# Robot_Arm_Controller.net
KiCad netlist of a schematic drawn in EAGLE
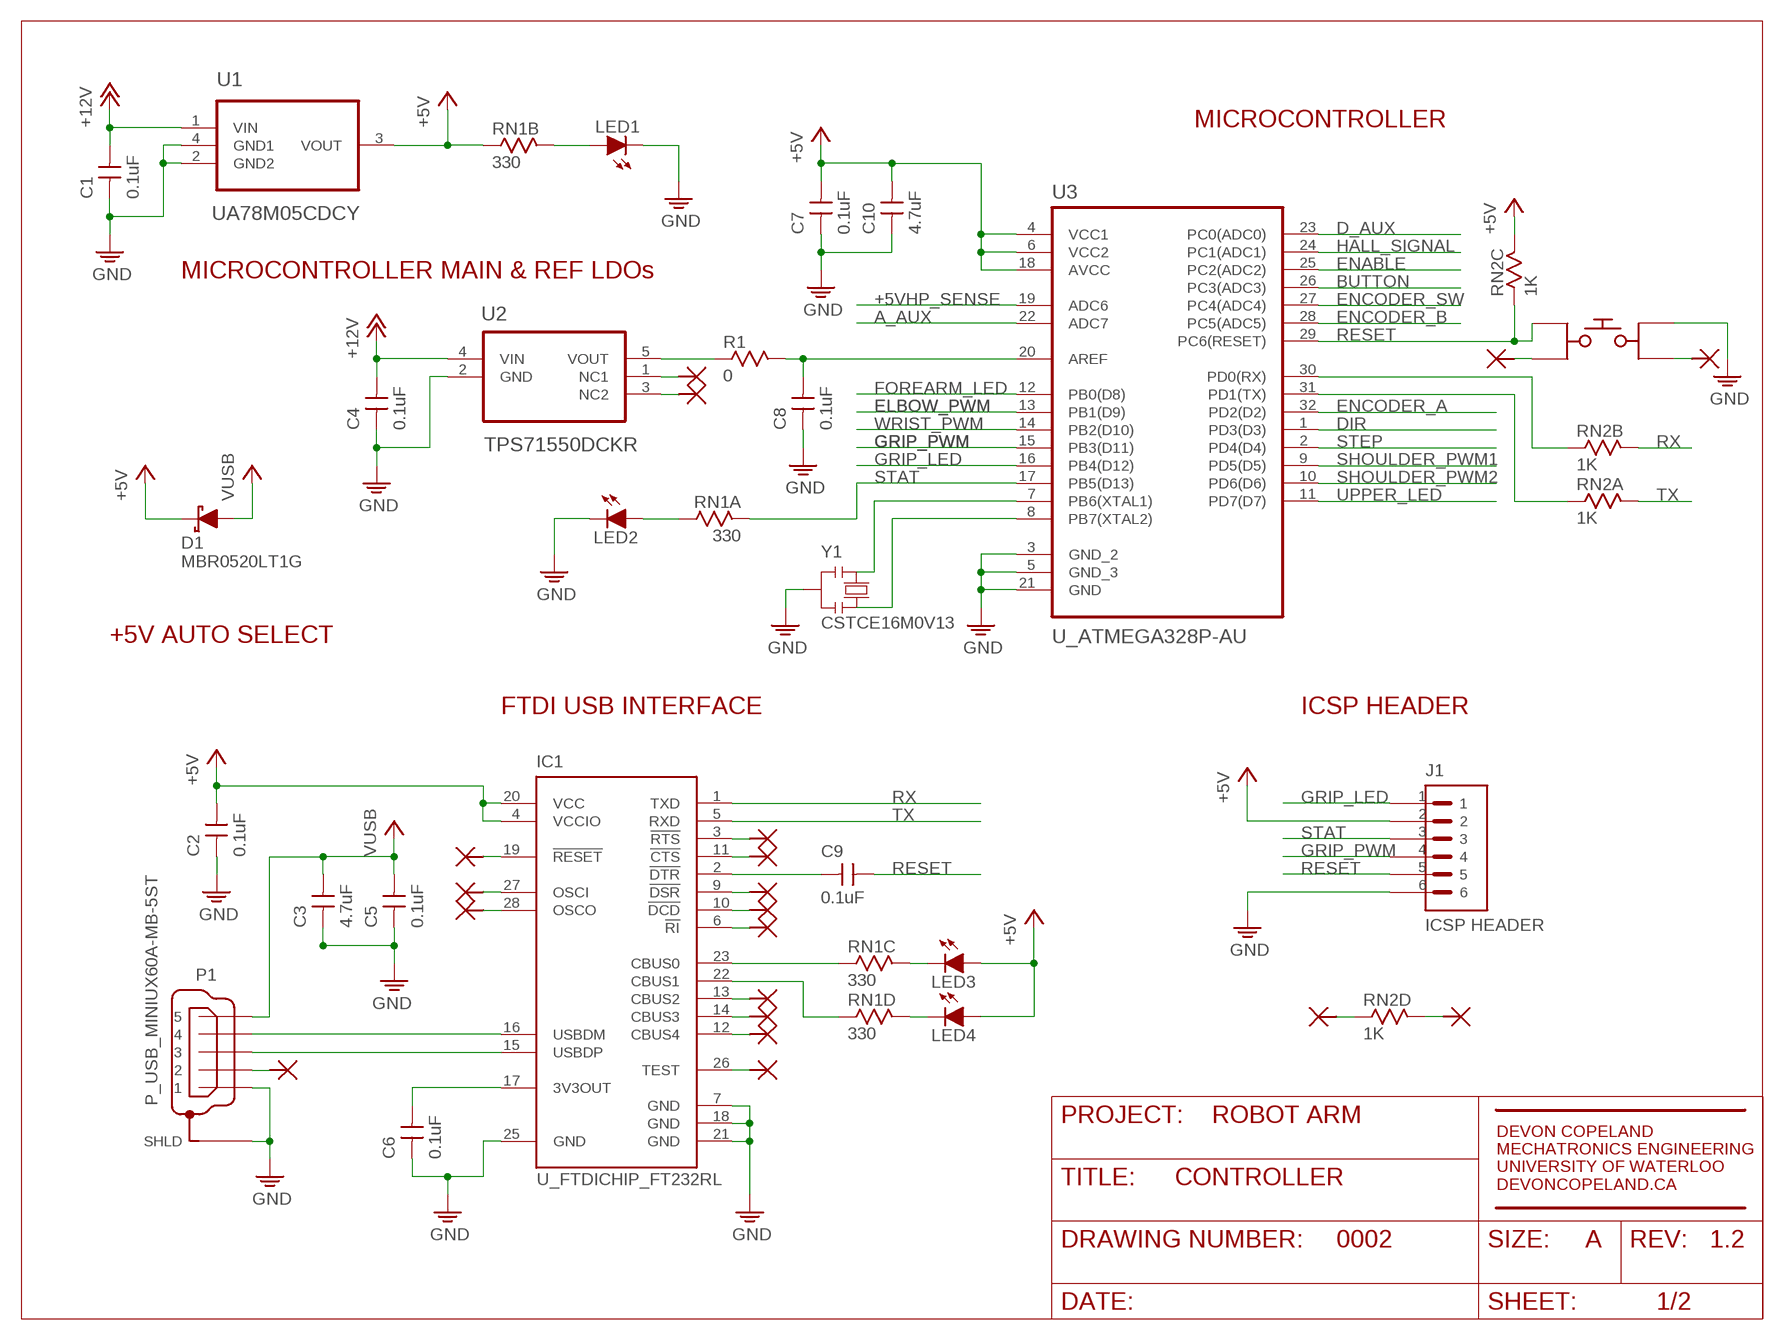
[diagram p0: schematic, sheet 1]
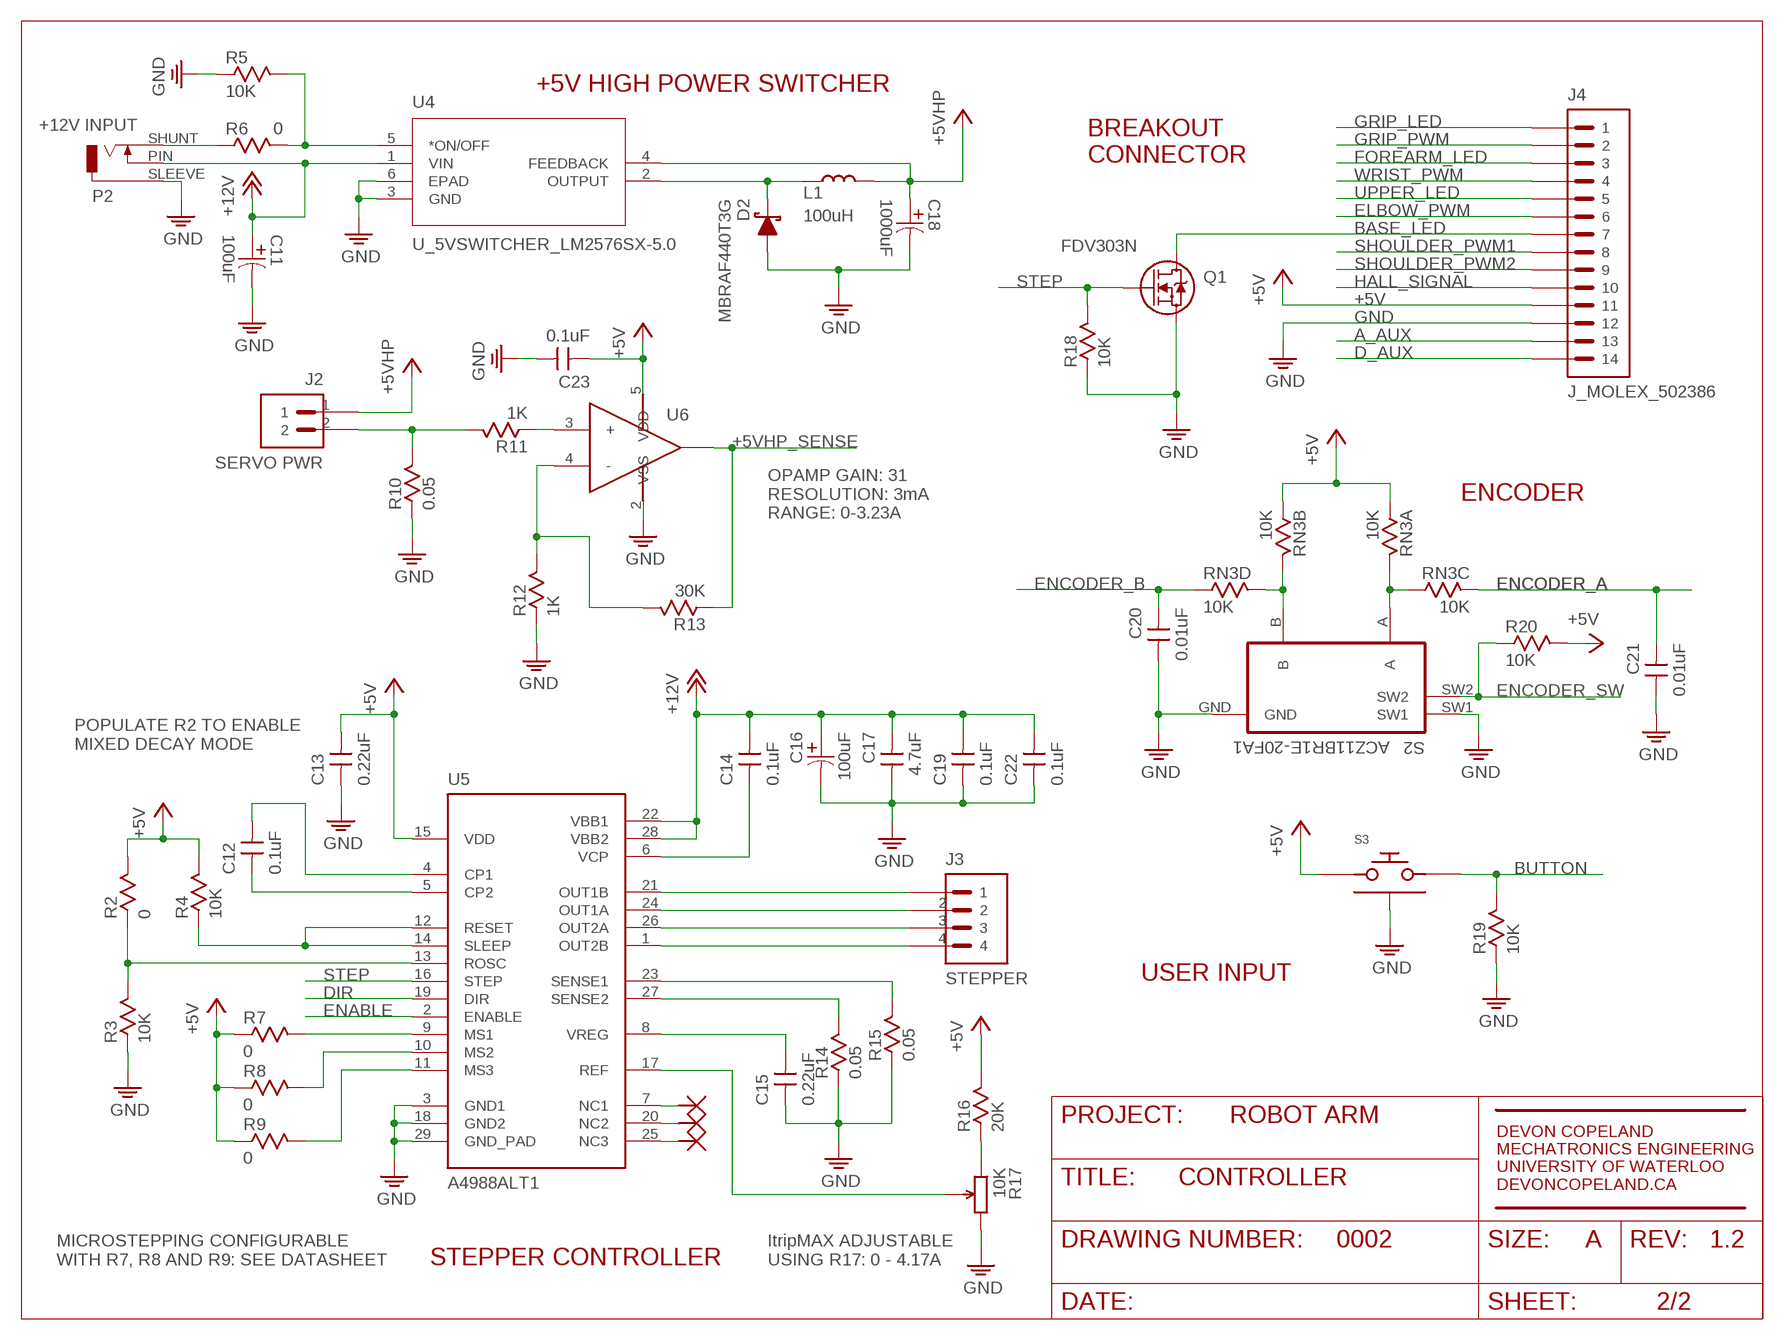
[diagram p1: schematic, sheet 2]

(export (version "E")
  (design (tool "Eeschema 10.0.6"))
  (components
    (comp (ref "C1")
      (value "0.1uF")
      (footprint "eagle-import:C0805")
      (libsource (lib "eagle-import") (part "C_CAPACITORC0805"))
    )
    (comp (ref "C2")
      (value "0.1uF")
      (footprint "eagle-import:C0805")
      (libsource (lib "eagle-import") (part "C_CAPACITORC0805"))
    )
    (comp (ref "C3")
      (value "4.7uF")
      (footprint "eagle-import:C0805")
      (libsource (lib "eagle-import") (part "C_CAPACITORC0805"))
    )
    (comp (ref "C4")
      (value "0.1uF")
      (footprint "eagle-import:C0805")
      (libsource (lib "eagle-import") (part "C_CAPACITORC0805"))
    )
    (comp (ref "C5")
      (value "0.1uF")
      (footprint "eagle-import:C0805")
      (libsource (lib "eagle-import") (part "C_CAPACITORC0805"))
    )
    (comp (ref "C6")
      (value "0.1uF")
      (footprint "eagle-import:C0805")
      (libsource (lib "eagle-import") (part "C_CAPACITORC0805"))
    )
    (comp (ref "C7")
      (value "0.1uF")
      (footprint "eagle-import:C0805")
      (libsource (lib "eagle-import") (part "C_CAPACITORC0805"))
    )
    (comp (ref "C8")
      (value "0.1uF")
      (footprint "eagle-import:C0805")
      (libsource (lib "eagle-import") (part "C_CAPACITORC0805"))
    )
    (comp (ref "C9")
      (value "0.1uF")
      (footprint "eagle-import:C0805")
      (libsource (lib "eagle-import") (part "C_CAPACITORC0805"))
    )
    (comp (ref "C10")
      (value "4.7uF")
      (footprint "eagle-import:C0805")
      (libsource (lib "eagle-import") (part "C_CAPACITORC0805"))
    )
    (comp (ref "D1")
      (value "MBR0520LT1G")
      (footprint "eagle-import:MBR0520LT1G")
      (libsource (lib "eagle-import") (part "D_SCHOTTKY_MBR0520LT1G"))
    )
    (comp (ref "IC1")
      (value "U_FTDICHIP_FT232RL")
      (footprint "eagle-import:SSOP28")
      (fields (field (name "MPN") "FT232RL"))
      (libsource (lib "eagle-import") (part "U_FTDICHIP_FT232RL"))
    )
    (comp (ref "J1")
      (value "ICSP HEADER")
      (footprint "eagle-import:RECTANGULAR_HEADER_2X3")
      (libsource (lib "eagle-import") (part "J_HEADER_RECTANGULAR_2X6"))
    )
    (comp (ref "LED1")
      (value "D_LEDSML0805")
      (footprint "eagle-import:SML0805")
      (libsource (lib "eagle-import") (part "D_LEDSML0805"))
    )
    (comp (ref "LED2")
      (value "D_LEDSML0805")
      (footprint "eagle-import:SML0805")
      (libsource (lib "eagle-import") (part "D_LEDSML0805"))
    )
    (comp (ref "LED3")
      (value "D_LEDSML0805")
      (footprint "eagle-import:SML0805")
      (libsource (lib "eagle-import") (part "D_LEDSML0805"))
    )
    (comp (ref "LED4")
      (value "D_LEDSML0805")
      (footprint "eagle-import:SML0805")
      (libsource (lib "eagle-import") (part "D_LEDSML0805"))
    )
    (comp (ref "P1")
      (value "P_USB_MINIUX60A-MB-5ST")
      (footprint "eagle-import:UX60A-MB-5ST")
      (libsource (lib "eagle-import") (part "P_USB_MINIUX60A-MB-5ST"))
    )
    (comp (ref "R1")
      (value "0")
      (footprint "eagle-import:R0805")
      (libsource (lib "eagle-import") (part "R_RESISTOR0805"))
    )
    (comp (ref "RN1")
      (value "330")
      (footprint "eagle-import:EXBV8V")
      (libsource (lib "eagle-import") (part "R_RESISTOR_NETWORK_EXB-V8V103JV"))
    )
    (comp (ref "RN2")
      (value "1K")
      (footprint "eagle-import:EXBV8V")
      (libsource (lib "eagle-import") (part "R_RESISTOR_NETWORK_EXB-V8V103JV"))
    )
    (comp (ref "S1")
      (value "S_BUTTON_TACTILE_PTS645")
      (footprint "eagle-import:PTS645-SMD")
      (libsource (lib "eagle-import") (part "S_BUTTON_TACTILE_PTS645"))
    )
    (comp (ref "U1")
      (value "UA78M05CDCY")
      (footprint "eagle-import:SOT230P700X180-4N")
      (libsource (lib "eagle-import") (part "U_5VLDO_UA78M05CDCY"))
    )
    (comp (ref "U2")
      (value "TPS71550DCKR")
      (footprint "eagle-import:SOT65P210X110-5N")
      (libsource (lib "eagle-import") (part "U_5VLDO_TPS71550DCKR"))
    )
    (comp (ref "U3")
      (value "U_ATMEGA328P-AU")
      (footprint "eagle-import:QFP80P900X900X120-32N")
      (fields (field (name "MPN") "ATMEGA328P-AU"))
      (libsource (lib "eagle-import") (part "U_ATMEGA328P-AU"))
    )
    (comp (ref "Y1")
      (value "CSTCE16M0V13")
      (footprint "eagle-import:CSTCE_V13L")
      (libsource (lib "eagle-import") (part "G_RESONATORMU"))
    )
    (comp (ref "C11")
      (value "100uF")
      (footprint "eagle-import:NPCAP_PXG_E61")
      (libsource (lib "eagle-import") (part "C_100UF_ALUMINUM_APXG160ARA101ME61G"))
    )
    (comp (ref "C12")
      (value "0.1uF")
      (footprint "eagle-import:C0805")
      (libsource (lib "eagle-import") (part "C_CAPACITORC0805"))
    )
    (comp (ref "C13")
      (value "0.22uF")
      (footprint "eagle-import:C0805")
      (libsource (lib "eagle-import") (part "C_CAPACITORC0805"))
    )
    (comp (ref "C14")
      (value "0.1uF")
      (footprint "eagle-import:C0805")
      (libsource (lib "eagle-import") (part "C_CAPACITORC0805"))
    )
    (comp (ref "C15")
      (value "0.22uF")
      (footprint "eagle-import:C0805")
      (libsource (lib "eagle-import") (part "C_CAPACITORC0805"))
    )
    (comp (ref "C16")
      (value "100uF")
      (footprint "eagle-import:NPCAP_PXG_E61")
      (libsource (lib "eagle-import") (part "C_100UF_ALUMINUM_APXG160ARA101ME61G"))
    )
    (comp (ref "C17")
      (value "4.7uF")
      (footprint "eagle-import:C0805")
      (libsource (lib "eagle-import") (part "C_CAPACITORC0805"))
    )
    (comp (ref "C18")
      (value "1000uF")
      (footprint "eagle-import:NPCAP_PXG_JA0")
      (libsource (lib "eagle-import") (part "C_1000UF_ALUMINUM_APXG160ARA102MJA0G"))
    )
    (comp (ref "C19")
      (value "0.1uF")
      (footprint "eagle-import:C0805")
      (libsource (lib "eagle-import") (part "C_CAPACITORC0805"))
    )
    (comp (ref "C20")
      (value "0.01uF")
      (footprint "eagle-import:C0805")
      (libsource (lib "eagle-import") (part "C_CAPACITORC0805"))
    )
    (comp (ref "C21")
      (value "0.01uF")
      (footprint "eagle-import:C0805")
      (libsource (lib "eagle-import") (part "C_CAPACITORC0805"))
    )
    (comp (ref "C22")
      (value "0.1uF")
      (footprint "eagle-import:C0805")
      (libsource (lib "eagle-import") (part "C_CAPACITORC0805"))
    )
    (comp (ref "C23")
      (value "0.1uF")
      (footprint "eagle-import:C0805")
      (libsource (lib "eagle-import") (part "C_CAPACITORC0805"))
    )
    (comp (ref "D2")
      (value "MBRAF440T3G")
      (footprint "eagle-import:MBRAF440T3G")
      (libsource (lib "eagle-import") (part "D_SCHOTTKY_MBRAF440T3G"))
    )
    (comp (ref "J2")
      (value "SERVO PWR")
      (footprint "eagle-import:SREW_TERMINAL_2_POS")
      (libsource (lib "eagle-import") (part "J_SCREW_TERMINAL_2_POS"))
    )
    (comp (ref "J3")
      (value "STEPPER")
      (footprint "eagle-import:SREW_TERMINAL_4_POS")
      (libsource (lib "eagle-import") (part "J_SCREW_TERMINAL_4_POS"))
    )
    (comp (ref "J4")
      (value "J_MOLEX_502386")
      (footprint "eagle-import:MOLEX_502386")
      (libsource (lib "eagle-import") (part "J_MOLEX_502386"))
    )
    (comp (ref "L1")
      (value "100uH")
      (footprint "eagle-import:PA4344.104NLT")
      (libsource (lib "eagle-import") (part "L_INDUCTOR_PA4344.104NLT"))
    )
    (comp (ref "P2")
      (value "+12V INPUT")
      (footprint "eagle-import:RASM722PX")
      (libsource (lib "eagle-import") (part "P_BARREL_2.1MM"))
    )
    (comp (ref "Q1")
      (value "FDV303N")
      (footprint "eagle-import:SOT-23-3L")
      (fields (field (name "COPYRIGHT") "Copyright C 2015 Accelerated Designs. All rights reserved"))
      (libsource (lib "eagle-import") (part "Q_MOSFET_FDV303N"))
    )
    (comp (ref "R2")
      (value "0")
      (footprint "eagle-import:R0805")
      (libsource (lib "eagle-import") (part "R_RESISTOR0805"))
    )
    (comp (ref "R3")
      (value "10K")
      (footprint "eagle-import:R0805")
      (libsource (lib "eagle-import") (part "R_RESISTOR0805"))
    )
    (comp (ref "R4")
      (value "10K")
      (footprint "eagle-import:R0805")
      (libsource (lib "eagle-import") (part "R_RESISTOR0805"))
    )
    (comp (ref "R5")
      (value "10K")
      (footprint "eagle-import:R0805")
      (libsource (lib "eagle-import") (part "R_RESISTOR0805"))
    )
    (comp (ref "R6")
      (value "0")
      (footprint "eagle-import:R0805")
      (libsource (lib "eagle-import") (part "R_RESISTOR0805"))
    )
    (comp (ref "R7")
      (value "0")
      (footprint "eagle-import:R0805")
      (libsource (lib "eagle-import") (part "R_RESISTOR0805"))
    )
    (comp (ref "R8")
      (value "0")
      (footprint "eagle-import:R0805")
      (libsource (lib "eagle-import") (part "R_RESISTOR0805"))
    )
    (comp (ref "R9")
      (value "0")
      (footprint "eagle-import:R0805")
      (libsource (lib "eagle-import") (part "R_RESISTOR0805"))
    )
    (comp (ref "R10")
      (value "0.05")
      (footprint "eagle-import:R1206")
      (libsource (lib "eagle-import") (part "R_RESISTOR1206"))
    )
    (comp (ref "R11")
      (value "1K")
      (footprint "eagle-import:R0805")
      (libsource (lib "eagle-import") (part "R_RESISTOR0805"))
    )
    (comp (ref "R12")
      (value "1K")
      (footprint "eagle-import:R0805")
      (libsource (lib "eagle-import") (part "R_RESISTOR0805"))
    )
    (comp (ref "R13")
      (value "30K")
      (footprint "eagle-import:R0805")
      (libsource (lib "eagle-import") (part "R_RESISTOR0805"))
    )
    (comp (ref "R14")
      (value "0.05")
      (footprint "eagle-import:R1206")
      (libsource (lib "eagle-import") (part "R_RESISTOR1206"))
    )
    (comp (ref "R15")
      (value "0.05")
      (footprint "eagle-import:R1206")
      (libsource (lib "eagle-import") (part "R_RESISTOR1206"))
    )
    (comp (ref "R16")
      (value "20K")
      (footprint "eagle-import:R0805")
      (libsource (lib "eagle-import") (part "R_RESISTOR0805"))
    )
    (comp (ref "R17")
      (value "10K")
      (footprint "eagle-import:PANASONIC_P2W_POT")
      (libsource (lib "eagle-import") (part "R_POT_EVM-2WSX80B14"))
    )
    (comp (ref "R18")
      (value "10K")
      (footprint "eagle-import:R0805")
      (libsource (lib "eagle-import") (part "R_RESISTOR0805"))
    )
    (comp (ref "R19")
      (value "10K")
      (footprint "eagle-import:R0805")
      (libsource (lib "eagle-import") (part "R_RESISTOR0805"))
    )
    (comp (ref "R20")
      (value "10K")
      (footprint "eagle-import:R0805")
      (libsource (lib "eagle-import") (part "R_RESISTOR0805"))
    )
    (comp (ref "RN3")
      (value "10K")
      (footprint "eagle-import:EXBV8V")
      (libsource (lib "eagle-import") (part "R_RESISTOR_NETWORK_EXB-V8V103JV"))
    )
    (comp (ref "S2")
      (value "ACZ11BR1E-20FA1")
      (footprint "eagle-import:ACZ11BR1E-20FA1-20C")
      (libsource (lib "eagle-import") (part "S_ENCODER_ACZ11BR1E-20FA1-20C"))
    )
    (comp (ref "S3")
      (value "S_BUTTON_TACTILE_KT11S1SA2M35LFG")
      (footprint "eagle-import:C&K_SA2M_SA1M")
      (libsource (lib "eagle-import") (part "S_BUTTON_TACTILE_KT11S1SA2M35LFG"))
    )
    (comp (ref "U4")
      (value "U_5VSWITCHER_LM2576SX-5.0")
      (footprint "eagle-import:KTT5_6P22X6P86")
      (fields
        (field (name "GENERIC_PART_NUMBER") "TL257505")
        (field (name "MANUFACTURER") "Texas Instruments")
        (field (name "MANUFACTURER_PART_NUMBER") "tl257505_ktt_5")
        (field (name "COPYRIGHT") "Copyright C 2015 Accelerated Designs. All rights reserved")
      )
      (libsource (lib "eagle-import") (part "U_5VSWITCHER_LM2576SX-5.0/NOPB"))
    )
    (comp (ref "U5")
      (value "A4988ALT1")
      (footprint "eagle-import:ALLEGRO_A4988")
      (libsource (lib "eagle-import") (part "U_STEPPER_DRIVER_A4988ALT1"))
    )
    (comp (ref "U6")
      (value "U_OPAMP_MCP6001T-E/OT")
      (footprint "eagle-import:SOT95P270X145-5N")
      (fields (field (name "MPN") "MCP6001T-E/OT"))
      (libsource (lib "eagle-import") (part "U_OPAMP_MCP6001T-E/OT"))
    )
  )
  (nets
    (net (code "1") (name "+5V") (class "Default")
      (node (ref "C10") (pin "1") (pinfunction "1_1") (pintype "passive"))
      (node (ref "C13") (pin "1") (pinfunction "1_1") (pintype "passive"))
      (node (ref "C2") (pin "1") (pinfunction "1_1") (pintype "passive"))
      (node (ref "C23") (pin "2") (pinfunction "2_2") (pintype "passive"))
      (node (ref "C7") (pin "1") (pinfunction "1_1") (pintype "passive"))
      (node (ref "D1") (pin "C") (pinfunction "C_C") (pintype "passive"))
      (node (ref "IC1") (pin "20") (pinfunction "VCC_20") (pintype "power_in"))
      (node (ref "IC1") (pin "4") (pinfunction "VCCIO_4") (pintype "power_in"))
      (node (ref "J1") (pin "2") (pinfunction "2_2") (pintype "bidirectional"))
      (node (ref "J4") (pin "P11") (pinfunction "11_P11") (pintype "bidirectional"))
      (node (ref "LED3") (pin "A") (pinfunction "A_A") (pintype "passive"))
      (node (ref "LED4") (pin "A") (pinfunction "A_A") (pintype "passive"))
      (node (ref "R16") (pin "2") (pinfunction "2_2") (pintype "passive"))
      (node (ref "R2") (pin "2") (pinfunction "2_2") (pintype "passive"))
      (node (ref "R20") (pin "2") (pinfunction "2_2") (pintype "passive"))
      (node (ref "R4") (pin "2") (pinfunction "2_2") (pintype "passive"))
      (node (ref "R7") (pin "1") (pinfunction "1_1") (pintype "passive"))
      (node (ref "R8") (pin "1") (pinfunction "1_1") (pintype "passive"))
      (node (ref "R9") (pin "1") (pinfunction "1_1") (pintype "passive"))
      (node (ref "RN1") (pin "2A") (pinfunction "1_2A") (pintype "passive"))
      (node (ref "RN2") (pin "3B") (pinfunction "2_3B") (pintype "passive"))
      (node (ref "RN3") (pin "1A") (pinfunction "1_1A") (pintype "passive"))
      (node (ref "RN3") (pin "2A") (pinfunction "1_2A") (pintype "passive"))
      (node (ref "S3") (pin "1") (pinfunction "1_1") (pintype "bidirectional"))
      (node (ref "U1") (pin "3") (pinfunction "VOUT_3") (pintype "input"))
      (node (ref "U3") (pin "18") (pinfunction "AVCC_18") (pintype "power_in"))
      (node (ref "U3") (pin "4") (pinfunction "VCC1_4") (pintype "power_in"))
      (node (ref "U3") (pin "6") (pinfunction "VCC2_6") (pintype "power_in"))
      (node (ref "U5") (pin "15") (pinfunction "VDD_15") (pintype "power_in"))
      (node (ref "U6") (pin "5") (pinfunction "VDD_5") (pintype "power_in"))
    )
    (net (code "2") (name "+5VHP") (class "Default")
      (node (ref "C18") (pin "+") (pinfunction "+_+") (pintype "passive"))
      (node (ref "J2") (pin "1") (pinfunction "1_1") (pintype "bidirectional"))
      (node (ref "L1") (pin "2") (pinfunction "2_2") (pintype "passive"))
      (node (ref "U4") (pin "4") (pinfunction "FEEDBACK_4") (pintype "passive"))
    )
    (net (code "3") (name "+5VHP_SENSE") (class "Default")
      (node (ref "R13") (pin "1") (pinfunction "1_1") (pintype "passive"))
      (node (ref "U3") (pin "19") (pinfunction "ADC6_19") (pintype "input"))
      (node (ref "U6") (pin "1") (pinfunction "VOUT_1") (pintype "output"))
    )
    (net (code "4") (name "+12V") (class "Default")
      (node (ref "C1") (pin "1") (pinfunction "1_1") (pintype "passive"))
      (node (ref "C11") (pin "+") (pinfunction "+_+") (pintype "passive"))
      (node (ref "C14") (pin "1") (pinfunction "1_1") (pintype "passive"))
      (node (ref "C16") (pin "+") (pinfunction "+_+") (pintype "passive"))
      (node (ref "C17") (pin "2") (pinfunction "2_2") (pintype "passive"))
      (node (ref "C19") (pin "1") (pinfunction "1_1") (pintype "passive"))
      (node (ref "C22") (pin "1") (pinfunction "1_1") (pintype "passive"))
      (node (ref "C4") (pin "1") (pinfunction "1_1") (pintype "passive"))
      (node (ref "P2") (pin "PIN") (pinfunction "PIN_PIN") (pintype "passive"))
      (node (ref "U1") (pin "1") (pinfunction "VIN_1") (pintype "input"))
      (node (ref "U2") (pin "4") (pinfunction "VIN_4") (pintype "power_in"))
      (node (ref "U4") (pin "1") (pinfunction "VIN_1") (pintype "input"))
      (node (ref "U5") (pin "22") (pinfunction "VBB1_22") (pintype "bidirectional"))
      (node (ref "U5") (pin "28") (pinfunction "VBB2_28") (pintype "bidirectional"))
    )
    (net (code "5") (name "A_AUX") (class "Default")
      (node (ref "J4") (pin "P13") (pinfunction "13_P13") (pintype "bidirectional"))
      (node (ref "U3") (pin "22") (pinfunction "ADC7_22") (pintype "input"))
    )
    (net (code "6") (name "BASE_LED") (class "Default")
      (node (ref "J4") (pin "P7") (pinfunction "7_P7") (pintype "bidirectional"))
      (node (ref "Q1") (pin "S") (pinfunction "DRAIN_S") (pintype "passive"))
    )
    (net (code "7") (name "BUTTON") (class "Default")
      (node (ref "R19") (pin "2") (pinfunction "2_2") (pintype "passive"))
      (node (ref "S3") (pin "2") (pinfunction "2_2") (pintype "bidirectional"))
      (node (ref "U3") (pin "26") (pinfunction "PC3(ADC3)_26") (pintype "bidirectional"))
    )
    (net (code "8") (name "DIR") (class "Default")
      (node (ref "U3") (pin "1") (pinfunction "PD3(D3)_1") (pintype "bidirectional"))
      (node (ref "U5") (pin "19") (pinfunction "DIR_19") (pintype "input"))
    )
    (net (code "9") (name "D_AUX") (class "Default")
      (node (ref "J4") (pin "P14") (pinfunction "14_P14") (pintype "bidirectional"))
      (node (ref "U3") (pin "23") (pinfunction "PC0(ADC0)_23") (pintype "bidirectional"))
    )
    (net (code "10") (name "ELBOW_PWM") (class "Default")
      (node (ref "J4") (pin "P6") (pinfunction "6_P6") (pintype "bidirectional"))
      (node (ref "U3") (pin "13") (pinfunction "PB1(D9)_13") (pintype "bidirectional"))
    )
    (net (code "11") (name "ENABLE") (class "Default")
      (node (ref "U3") (pin "25") (pinfunction "PC2(ADC2)_25") (pintype "bidirectional"))
      (node (ref "U5") (pin "2") (pinfunction "ENABLE_2") (pintype "input"))
    )
    (net (code "12") (name "ENCODER_A") (class "Default")
      (node (ref "C21") (pin "2") (pinfunction "2_2") (pintype "passive"))
      (node (ref "RN3") (pin "3A") (pinfunction "1_3A") (pintype "passive"))
      (node (ref "U3") (pin "32") (pinfunction "PD2(D2)_32") (pintype "bidirectional"))
    )
    (net (code "13") (name "ENCODER_B") (class "Default")
      (node (ref "C20") (pin "2") (pinfunction "2_2") (pintype "passive"))
      (node (ref "RN3") (pin "4A") (pinfunction "1_4A") (pintype "passive"))
      (node (ref "U3") (pin "28") (pinfunction "PC5(ADC5)_28") (pintype "bidirectional"))
    )
    (net (code "14") (name "ENCODER_SW") (class "Default")
      (node (ref "R20") (pin "1") (pinfunction "1_1") (pintype "passive"))
      (node (ref "S2") (pin "SW2") (pinfunction "SW2_SW2") (pintype "output"))
      (node (ref "U3") (pin "27") (pinfunction "PC4(ADC4)_27") (pintype "bidirectional"))
    )
    (net (code "15") (name "FOREARM_LED") (class "Default")
      (node (ref "J4") (pin "P3") (pinfunction "3_P3") (pintype "bidirectional"))
      (node (ref "U3") (pin "12") (pinfunction "PB0(D8)_12") (pintype "bidirectional"))
    )
    (net (code "16") (name "GND") (class "Default")
      (node (ref "C1") (pin "2") (pinfunction "2_2") (pintype "passive"))
      (node (ref "C10") (pin "2") (pinfunction "2_2") (pintype "passive"))
      (node (ref "C11") (pin "-") (pinfunction "-_-") (pintype "passive"))
      (node (ref "C13") (pin "2") (pinfunction "2_2") (pintype "passive"))
      (node (ref "C15") (pin "2") (pinfunction "2_2") (pintype "passive"))
      (node (ref "C16") (pin "-") (pinfunction "-_-") (pintype "passive"))
      (node (ref "C17") (pin "1") (pinfunction "1_1") (pintype "passive"))
      (node (ref "C18") (pin "-") (pinfunction "-_-") (pintype "passive"))
      (node (ref "C19") (pin "2") (pinfunction "2_2") (pintype "passive"))
      (node (ref "C2") (pin "2") (pinfunction "2_2") (pintype "passive"))
      (node (ref "C20") (pin "1") (pinfunction "1_1") (pintype "passive"))
      (node (ref "C21") (pin "1") (pinfunction "1_1") (pintype "passive"))
      (node (ref "C22") (pin "2") (pinfunction "2_2") (pintype "passive"))
      (node (ref "C23") (pin "1") (pinfunction "1_1") (pintype "passive"))
      (node (ref "C3") (pin "2") (pinfunction "2_2") (pintype "passive"))
      (node (ref "C4") (pin "2") (pinfunction "2_2") (pintype "passive"))
      (node (ref "C5") (pin "2") (pinfunction "2_2") (pintype "passive"))
      (node (ref "C6") (pin "2") (pinfunction "2_2") (pintype "passive"))
      (node (ref "C7") (pin "2") (pinfunction "2_2") (pintype "passive"))
      (node (ref "C8") (pin "2") (pinfunction "2_2") (pintype "passive"))
      (node (ref "D2") (pin "A") (pinfunction "A_A") (pintype "passive"))
      (node (ref "IC1") (pin "18") (pinfunction "GND_18") (pintype "power_in"))
      (node (ref "IC1") (pin "21") (pinfunction "GND_21") (pintype "power_in"))
      (node (ref "IC1") (pin "25") (pinfunction "GND_25") (pintype "power_in"))
      (node (ref "IC1") (pin "7") (pinfunction "GND_7") (pintype "power_in"))
      (node (ref "J1") (pin "6") (pinfunction "6_6") (pintype "bidirectional"))
      (node (ref "J4") (pin "P12") (pinfunction "12_P12") (pintype "bidirectional"))
      (node (ref "LED1") (pin "C") (pinfunction "C_C") (pintype "passive"))
      (node (ref "LED2") (pin "C") (pinfunction "C_C") (pintype "passive"))
      (node (ref "P1") (pin "5") (pinfunction "1_5") (pintype "input"))
      (node (ref "P1") (pin "M1") (pinfunction "SHLD_M1") (pintype "bidirectional"))
      (node (ref "P1") (pin "M2") (pinfunction "SHLD_M2") (pintype "bidirectional"))
      (node (ref "P1") (pin "M3") (pinfunction "SHLD_M3") (pintype "bidirectional"))
      (node (ref "P1") (pin "M4") (pinfunction "SHLD_M4") (pintype "bidirectional"))
      (node (ref "P2") (pin "SLEEVE") (pinfunction "SLEEVE_SLEEVE") (pintype "passive"))
      (node (ref "Q1") (pin "D") (pinfunction "SOURCE_D") (pintype "passive"))
      (node (ref "R10") (pin "1") (pinfunction "1_1") (pintype "passive"))
      (node (ref "R12") (pin "1") (pinfunction "1_1") (pintype "passive"))
      (node (ref "R14") (pin "1") (pinfunction "1_1") (pintype "passive"))
      (node (ref "R15") (pin "1") (pinfunction "1_1") (pintype "passive"))
      (node (ref "R17") (pin "3") (pinfunction "3_3") (pintype "passive"))
      (node (ref "R18") (pin "1") (pinfunction "1_1") (pintype "passive"))
      (node (ref "R19") (pin "1") (pinfunction "1_1") (pintype "passive"))
      (node (ref "R3") (pin "1") (pinfunction "1_1") (pintype "passive"))
      (node (ref "R5") (pin "1") (pinfunction "1_1") (pintype "passive"))
      (node (ref "S1") (pin "1") (pinfunction "1_1") (pintype "bidirectional"))
      (node (ref "S2") (pin "GND") (pinfunction "GND_GND") (pintype "output"))
      (node (ref "S2") (pin "SW1") (pinfunction "SW1_SW1") (pintype "input"))
      (node (ref "S3") (pin "FRONT") (pinfunction "HOUSING_FRONT") (pintype "passive"))
      (node (ref "S3") (pin "SIDE1") (pinfunction "HOUSING_SIDE1") (pintype "passive"))
      (node (ref "S3") (pin "SIDE2") (pinfunction "HOUSING_SIDE2") (pintype "passive"))
      (node (ref "U1") (pin "2") (pinfunction "GND2_2") (pintype "output"))
      (node (ref "U1") (pin "4") (pinfunction "GND1_4") (pintype "output"))
      (node (ref "U2") (pin "2") (pinfunction "GND_2") (pintype "power_in"))
      (node (ref "U3") (pin "21") (pinfunction "GND_21") (pintype "passive"))
      (node (ref "U3") (pin "3") (pinfunction "GND_2_3") (pintype "passive"))
      (node (ref "U3") (pin "5") (pinfunction "GND_3_5") (pintype "passive"))
      (node (ref "U4") (pin "3") (pinfunction "GND_3") (pintype "power_in"))
      (node (ref "U4") (pin "6") (pinfunction "EPAD_6") (pintype "passive"))
      (node (ref "U5") (pin "18") (pinfunction "GND2_18") (pintype "power_in"))
      (node (ref "U5") (pin "29") (pinfunction "GND_PAD_29") (pintype "power_in"))
      (node (ref "U5") (pin "3") (pinfunction "GND1_3") (pintype "power_in"))
      (node (ref "U6") (pin "2") (pinfunction "VSS_2") (pintype "passive"))
      (node (ref "Y1") (pin "2") (pinfunction "2_2") (pintype "passive"))
    )
    (net (code "17") (name "GRIP_LED") (class "Default")
      (node (ref "J1") (pin "1") (pinfunction "1_1") (pintype "bidirectional"))
      (node (ref "J4") (pin "P1") (pinfunction "1_P1") (pintype "bidirectional"))
      (node (ref "U3") (pin "16") (pinfunction "PB4(D12)_16") (pintype "bidirectional"))
    )
    (net (code "18") (name "GRIP_PWM") (class "Default")
      (node (ref "J1") (pin "4") (pinfunction "4_4") (pintype "bidirectional"))
      (node (ref "J4") (pin "P2") (pinfunction "2_P2") (pintype "bidirectional"))
      (node (ref "U3") (pin "15") (pinfunction "PB3(D11)_15") (pintype "bidirectional"))
    )
    (net (code "19") (name "HALL_SIGNAL") (class "Default")
      (node (ref "J4") (pin "P10") (pinfunction "10_P10") (pintype "bidirectional"))
      (node (ref "U3") (pin "24") (pinfunction "PC1(ADC1)_24") (pintype "bidirectional"))
    )
    (net (code "20") (name "Net-(IC1-3V3OUT)") (class "Default")
      (node (ref "C6") (pin "1") (pinfunction "1_1") (pintype "passive"))
      (node (ref "IC1") (pin "17") (pinfunction "3V3OUT_17") (pintype "output"))
    )
    (net (code "21") (name "Net-(IC1-CBUS0)") (class "Default")
      (node (ref "IC1") (pin "23") (pinfunction "CBUS0_23") (pintype "bidirectional"))
      (node (ref "RN1") (pin "3A") (pinfunction "1_3A") (pintype "passive"))
    )
    (net (code "22") (name "Net-(IC1-CBUS1)") (class "Default")
      (node (ref "IC1") (pin "22") (pinfunction "CBUS1_22") (pintype "bidirectional"))
      (node (ref "RN1") (pin "4A") (pinfunction "1_4A") (pintype "passive"))
    )
    (net (code "23") (name "Net-(IC1-USBDM)") (class "Default")
      (node (ref "IC1") (pin "16") (pinfunction "USBDM_16") (pintype "bidirectional"))
      (node (ref "P1") (pin "2") (pinfunction "4_2") (pintype "input"))
    )
    (net (code "24") (name "Net-(IC1-USBDP)") (class "Default")
      (node (ref "IC1") (pin "15") (pinfunction "USBDP_15") (pintype "bidirectional"))
      (node (ref "P1") (pin "3") (pinfunction "3_3") (pintype "input"))
    )
    (net (code "25") (name "Net-(IC1-~{DTR})") (class "Default")
      (node (ref "C9") (pin "2") (pinfunction "2_2") (pintype "passive"))
      (node (ref "IC1") (pin "2") (pinfunction "~{DTR}_2") (pintype "output"))
    )
    (net (code "26") (name "Net-(J2-Pad2)") (class "Default")
      (node (ref "J2") (pin "2") (pinfunction "2_2") (pintype "bidirectional"))
      (node (ref "R10") (pin "2") (pinfunction "2_2") (pintype "passive"))
      (node (ref "R11") (pin "2") (pinfunction "2_2") (pintype "passive"))
    )
    (net (code "27") (name "Net-(P2-PadSHUNT)") (class "Default")
      (node (ref "P2") (pin "SHUNT") (pinfunction "SHUNT_SHUNT") (pintype "passive"))
      (node (ref "R6") (pin "1") (pinfunction "1_1") (pintype "passive"))
    )
    (net (code "28") (name "Net-(R16-Pad1)") (class "Default")
      (node (ref "R16") (pin "1") (pinfunction "1_1") (pintype "passive"))
      (node (ref "R17") (pin "1") (pinfunction "1_1") (pintype "passive"))
    )
    (net (code "29") (name "Net-(RN1A-2)") (class "Default")
      (node (ref "LED2") (pin "A") (pinfunction "A_A") (pintype "passive"))
      (node (ref "RN1") (pin "1B") (pinfunction "2_1B") (pintype "passive"))
    )
    (net (code "30") (name "Net-(RN1B-2)") (class "Default")
      (node (ref "LED1") (pin "A") (pinfunction "A_A") (pintype "passive"))
      (node (ref "RN1") (pin "2B") (pinfunction "2_2B") (pintype "passive"))
    )
    (net (code "31") (name "Net-(RN1C-2)") (class "Default")
      (node (ref "LED3") (pin "C") (pinfunction "C_C") (pintype "passive"))
      (node (ref "RN1") (pin "3B") (pinfunction "2_3B") (pintype "passive"))
    )
    (net (code "32") (name "Net-(RN1D-2)") (class "Default")
      (node (ref "LED4") (pin "C") (pinfunction "C_C") (pintype "passive"))
      (node (ref "RN1") (pin "4B") (pinfunction "2_4B") (pintype "passive"))
    )
    (net (code "33") (name "Net-(RN2A-1)") (class "Default")
      (node (ref "RN2") (pin "1A") (pinfunction "1_1A") (pintype "passive"))
      (node (ref "U3") (pin "31") (pinfunction "PD1(TX)_31") (pintype "bidirectional"))
    )
    (net (code "34") (name "Net-(RN2B-1)") (class "Default")
      (node (ref "RN2") (pin "2A") (pinfunction "1_2A") (pintype "passive"))
      (node (ref "U3") (pin "30") (pinfunction "PD0(RX)_30") (pintype "bidirectional"))
    )
    (net (code "35") (name "Net-(RN3A-2)") (class "Default")
      (node (ref "RN3") (pin "1B") (pinfunction "2_1B") (pintype "passive"))
      (node (ref "RN3") (pin "3B") (pinfunction "2_3B") (pintype "passive"))
      (node (ref "S2") (pin "A") (pinfunction "A_A") (pintype "input"))
    )
    (net (code "36") (name "Net-(RN3B-2)") (class "Default")
      (node (ref "RN3") (pin "2B") (pinfunction "2_2B") (pintype "passive"))
      (node (ref "RN3") (pin "4B") (pinfunction "2_4B") (pintype "passive"))
      (node (ref "S2") (pin "B") (pinfunction "B_B") (pintype "input"))
    )
    (net (code "37") (name "Net-(U2-VOUT)") (class "Default")
      (node (ref "R1") (pin "1") (pinfunction "1_1") (pintype "passive"))
      (node (ref "U2") (pin "5") (pinfunction "VOUT_5") (pintype "output"))
    )
    (net (code "38") (name "Net-(U3-AREF)") (class "Default")
      (node (ref "C8") (pin "1") (pinfunction "1_1") (pintype "passive"))
      (node (ref "R1") (pin "2") (pinfunction "2_2") (pintype "passive"))
      (node (ref "U3") (pin "20") (pinfunction "AREF_20") (pintype "input"))
    )
    (net (code "39") (name "Net-(U3-PB6(XTAL1))") (class "Default")
      (node (ref "U3") (pin "7") (pinfunction "PB6(XTAL1)_7") (pintype "bidirectional"))
      (node (ref "Y1") (pin "1") (pinfunction "1_1") (pintype "passive"))
    )
    (net (code "40") (name "Net-(U3-PB7(XTAL2))") (class "Default")
      (node (ref "U3") (pin "8") (pinfunction "PB7(XTAL2)_8") (pintype "bidirectional"))
      (node (ref "Y1") (pin "3") (pinfunction "3_3") (pintype "passive"))
    )
    (net (code "41") (name "Net-(U4-*ON{slash}OFF)") (class "Default")
      (node (ref "R5") (pin "2") (pinfunction "2_2") (pintype "passive"))
      (node (ref "R6") (pin "2") (pinfunction "2_2") (pintype "passive"))
      (node (ref "U4") (pin "5") (pinfunction "*ON/OFF_5") (pintype "passive"))
    )
    (net (code "42") (name "Net-(U4-OUTPUT)") (class "Default")
      (node (ref "D2") (pin "C") (pinfunction "C_C") (pintype "passive"))
      (node (ref "L1") (pin "1") (pinfunction "1_1") (pintype "passive"))
      (node (ref "U4") (pin "2") (pinfunction "OUTPUT_2") (pintype "output"))
    )
    (net (code "43") (name "Net-(U5-CP1)") (class "Default")
      (node (ref "C12") (pin "1") (pinfunction "1_1") (pintype "passive"))
      (node (ref "U5") (pin "4") (pinfunction "CP1_4") (pintype "bidirectional"))
    )
    (net (code "44") (name "Net-(U5-CP2)") (class "Default")
      (node (ref "C12") (pin "2") (pinfunction "2_2") (pintype "passive"))
      (node (ref "U5") (pin "5") (pinfunction "CP2_5") (pintype "bidirectional"))
    )
    (net (code "45") (name "Net-(U5-MS1)") (class "Default")
      (node (ref "R7") (pin "2") (pinfunction "2_2") (pintype "passive"))
      (node (ref "U5") (pin "9") (pinfunction "MS1_9") (pintype "input"))
    )
    (net (code "46") (name "Net-(U5-MS2)") (class "Default")
      (node (ref "R8") (pin "2") (pinfunction "2_2") (pintype "passive"))
      (node (ref "U5") (pin "10") (pinfunction "MS2_10") (pintype "input"))
    )
    (net (code "47") (name "Net-(U5-MS3)") (class "Default")
      (node (ref "R9") (pin "2") (pinfunction "2_2") (pintype "passive"))
      (node (ref "U5") (pin "11") (pinfunction "MS3_11") (pintype "input"))
    )
    (net (code "48") (name "Net-(U5-OUT1A)") (class "Default")
      (node (ref "J3") (pin "2") (pinfunction "2_2") (pintype "bidirectional"))
      (node (ref "U5") (pin "24") (pinfunction "OUT1A_24") (pintype "bidirectional"))
    )
    (net (code "49") (name "Net-(U5-OUT1B)") (class "Default")
      (node (ref "J3") (pin "1") (pinfunction "1_1") (pintype "bidirectional"))
      (node (ref "U5") (pin "21") (pinfunction "OUT1B_21") (pintype "bidirectional"))
    )
    (net (code "50") (name "Net-(U5-OUT2A)") (class "Default")
      (node (ref "J3") (pin "3") (pinfunction "3_3") (pintype "bidirectional"))
      (node (ref "U5") (pin "26") (pinfunction "OUT2A_26") (pintype "bidirectional"))
    )
    (net (code "51") (name "Net-(U5-OUT2B)") (class "Default")
      (node (ref "J3") (pin "4") (pinfunction "4_4") (pintype "bidirectional"))
      (node (ref "U5") (pin "1") (pinfunction "OUT2B_1") (pintype "bidirectional"))
    )
    (net (code "52") (name "Net-(U5-REF)") (class "Default")
      (node (ref "R17") (pin "2") (pinfunction "2_2") (pintype "passive"))
      (node (ref "U5") (pin "17") (pinfunction "REF_17") (pintype "bidirectional"))
    )
    (net (code "53") (name "Net-(U5-RESET)") (class "Default")
      (node (ref "R4") (pin "1") (pinfunction "1_1") (pintype "passive"))
      (node (ref "U5") (pin "12") (pinfunction "RESET_12") (pintype "input"))
      (node (ref "U5") (pin "14") (pinfunction "SLEEP_14") (pintype "input"))
    )
    (net (code "54") (name "Net-(U5-ROSC)") (class "Default")
      (node (ref "R2") (pin "1") (pinfunction "1_1") (pintype "passive"))
      (node (ref "R3") (pin "2") (pinfunction "2_2") (pintype "passive"))
      (node (ref "U5") (pin "13") (pinfunction "ROSC_13") (pintype "bidirectional"))
    )
    (net (code "55") (name "Net-(U5-SENSE1)") (class "Default")
      (node (ref "R15") (pin "2") (pinfunction "2_2") (pintype "passive"))
      (node (ref "U5") (pin "23") (pinfunction "SENSE1_23") (pintype "bidirectional"))
    )
    (net (code "56") (name "Net-(U5-SENSE2)") (class "Default")
      (node (ref "R14") (pin "2") (pinfunction "2_2") (pintype "passive"))
      (node (ref "U5") (pin "27") (pinfunction "SENSE2_27") (pintype "bidirectional"))
    )
    (net (code "57") (name "Net-(U5-VCP)") (class "Default")
      (node (ref "C14") (pin "2") (pinfunction "2_2") (pintype "passive"))
      (node (ref "U5") (pin "6") (pinfunction "VCP_6") (pintype "bidirectional"))
    )
    (net (code "58") (name "Net-(U5-VREG)") (class "Default")
      (node (ref "C15") (pin "1") (pinfunction "1_1") (pintype "passive"))
      (node (ref "U5") (pin "8") (pinfunction "VREG_8") (pintype "bidirectional"))
    )
    (net (code "59") (name "Net-(U6-+)") (class "Default")
      (node (ref "R11") (pin "1") (pinfunction "1_1") (pintype "passive"))
      (node (ref "U6") (pin "3") (pinfunction "+_3") (pintype "input"))
    )
    (net (code "60") (name "Net-(U6--)") (class "Default")
      (node (ref "R12") (pin "2") (pinfunction "2_2") (pintype "passive"))
      (node (ref "R13") (pin "2") (pinfunction "2_2") (pintype "passive"))
      (node (ref "U6") (pin "4") (pinfunction "-_4") (pintype "input"))
    )
    (net (code "61") (name "RESET") (class "Default")
      (node (ref "C9") (pin "1") (pinfunction "1_1") (pintype "passive"))
      (node (ref "J1") (pin "5") (pinfunction "5_5") (pintype "bidirectional"))
      (node (ref "RN2") (pin "3A") (pinfunction "1_3A") (pintype "passive"))
      (node (ref "S1") (pin "3") (pinfunction "3_3") (pintype "bidirectional"))
      (node (ref "U3") (pin "29") (pinfunction "PC6(RESET)_29") (pintype "bidirectional"))
    )
    (net (code "62") (name "RX") (class "Default")
      (node (ref "IC1") (pin "1") (pinfunction "TXD_1") (pintype "output"))
      (node (ref "RN2") (pin "2B") (pinfunction "2_2B") (pintype "passive"))
    )
    (net (code "63") (name "SHOULDER_PWM1") (class "Default")
      (node (ref "J4") (pin "P8") (pinfunction "8_P8") (pintype "bidirectional"))
      (node (ref "U3") (pin "9") (pinfunction "PD5(D5)_9") (pintype "bidirectional"))
    )
    (net (code "64") (name "SHOULDER_PWM2") (class "Default")
      (node (ref "J4") (pin "P9") (pinfunction "9_P9") (pintype "bidirectional"))
      (node (ref "U3") (pin "10") (pinfunction "PD6(D6)_10") (pintype "bidirectional"))
    )
    (net (code "65") (name "STAT") (class "Default")
      (node (ref "J1") (pin "3") (pinfunction "3_3") (pintype "bidirectional"))
      (node (ref "RN1") (pin "1A") (pinfunction "1_1A") (pintype "passive"))
      (node (ref "U3") (pin "17") (pinfunction "PB5(D13)_17") (pintype "bidirectional"))
    )
    (net (code "66") (name "STEP") (class "Default")
      (node (ref "Q1") (pin "G") (pinfunction "GATE_G") (pintype "passive"))
      (node (ref "R18") (pin "2") (pinfunction "2_2") (pintype "passive"))
      (node (ref "U3") (pin "2") (pinfunction "PD4(D4)_2") (pintype "bidirectional"))
      (node (ref "U5") (pin "16") (pinfunction "STEP_16") (pintype "input"))
    )
    (net (code "67") (name "TX") (class "Default")
      (node (ref "IC1") (pin "5") (pinfunction "RXD_5") (pintype "input"))
      (node (ref "RN2") (pin "1B") (pinfunction "2_1B") (pintype "passive"))
    )
    (net (code "68") (name "UPPER_LED") (class "Default")
      (node (ref "J4") (pin "P5") (pinfunction "5_P5") (pintype "bidirectional"))
      (node (ref "U3") (pin "11") (pinfunction "PD7(D7)_11") (pintype "bidirectional"))
    )
    (net (code "69") (name "VUSB") (class "Default")
      (node (ref "C3") (pin "1") (pinfunction "1_1") (pintype "passive"))
      (node (ref "C5") (pin "1") (pinfunction "1_1") (pintype "passive"))
      (node (ref "D1") (pin "A") (pinfunction "A_A") (pintype "passive"))
      (node (ref "P1") (pin "1") (pinfunction "5_1") (pintype "input"))
    )
    (net (code "70") (name "WRIST_PWM") (class "Default")
      (node (ref "J4") (pin "P4") (pinfunction "4_P4") (pintype "bidirectional"))
      (node (ref "U3") (pin "14") (pinfunction "PB2(D10)_14") (pintype "bidirectional"))
    )
    (net (code "71") (name "unconnected-(IC1-CBUS2-Pad13)") (class "Default")
      (node (ref "IC1") (pin "13") (pinfunction "CBUS2_13") (pintype "bidirectional"))
    )
    (net (code "72") (name "unconnected-(IC1-CBUS3-Pad14)") (class "Default")
      (node (ref "IC1") (pin "14") (pinfunction "CBUS3_14") (pintype "bidirectional"))
    )
    (net (code "73") (name "unconnected-(IC1-CBUS4-Pad12)") (class "Default")
      (node (ref "IC1") (pin "12") (pinfunction "CBUS4_12") (pintype "bidirectional"))
    )
    (net (code "74") (name "unconnected-(IC1-OSCI-Pad27)") (class "Default")
      (node (ref "IC1") (pin "27") (pinfunction "OSCI_27") (pintype "input"))
    )
    (net (code "75") (name "unconnected-(IC1-OSCO-Pad28)") (class "Default")
      (node (ref "IC1") (pin "28") (pinfunction "OSCO_28") (pintype "output"))
    )
    (net (code "76") (name "unconnected-(IC1-TEST-Pad26)") (class "Default")
      (node (ref "IC1") (pin "26") (pinfunction "TEST_26") (pintype "input"))
    )
    (net (code "77") (name "unconnected-(IC1-~{CTS}-Pad11)") (class "Default")
      (node (ref "IC1") (pin "11") (pinfunction "~{CTS}_11") (pintype "input"))
    )
    (net (code "78") (name "unconnected-(IC1-~{DCD}-Pad10)") (class "Default")
      (node (ref "IC1") (pin "10") (pinfunction "~{DCD}_10") (pintype "input"))
    )
    (net (code "79") (name "unconnected-(IC1-~{DSR}-Pad9)") (class "Default")
      (node (ref "IC1") (pin "9") (pinfunction "~{DSR}_9") (pintype "input"))
    )
    (net (code "80") (name "unconnected-(IC1-~{RESET}-Pad19)") (class "Default")
      (node (ref "IC1") (pin "19") (pinfunction "~{RESET}_19") (pintype "input"))
    )
    (net (code "81") (name "unconnected-(IC1-~{RI}-Pad6)") (class "Default")
      (node (ref "IC1") (pin "6") (pinfunction "~{RI}_6") (pintype "input"))
    )
    (net (code "82") (name "unconnected-(IC1-~{RTS}-Pad3)") (class "Default")
      (node (ref "IC1") (pin "3") (pinfunction "~{RTS}_3") (pintype "output"))
    )
    (net (code "83") (name "unconnected-(P1-2-Pad4)") (class "Default")
      (node (ref "P1") (pin "4") (pinfunction "2_4") (pintype "input"))
    )
    (net (code "84") (name "unconnected-(RN2D-1-Pad4A)") (class "Default")
      (node (ref "RN2") (pin "4A") (pinfunction "1_4A") (pintype "passive"))
    )
    (net (code "85") (name "unconnected-(RN2D-2-Pad4B)") (class "Default")
      (node (ref "RN2") (pin "4B") (pinfunction "2_4B") (pintype "passive"))
    )
    (net (code "86") (name "unconnected-(S1-Pad2)") (class "Default")
      (node (ref "S1") (pin "2") (pinfunction "2_2") (pintype "bidirectional"))
    )
    (net (code "87") (name "unconnected-(S1-Pad4)") (class "Default")
      (node (ref "S1") (pin "4") (pinfunction "4_4") (pintype "bidirectional"))
    )
    (net (code "88") (name "unconnected-(U2-NC1-Pad1)") (class "Default")
      (node (ref "U2") (pin "1") (pinfunction "NC1_1") (pintype "no_connect"))
    )
    (net (code "89") (name "unconnected-(U2-NC2-Pad3)") (class "Default")
      (node (ref "U2") (pin "3") (pinfunction "NC2_3") (pintype "no_connect"))
    )
    (net (code "90") (name "unconnected-(U5-NC1-Pad7)") (class "Default")
      (node (ref "U5") (pin "7") (pinfunction "NC1_7") (pintype "no_connect"))
    )
    (net (code "91") (name "unconnected-(U5-NC2-Pad20)") (class "Default")
      (node (ref "U5") (pin "20") (pinfunction "NC2_20") (pintype "no_connect"))
    )
    (net (code "92") (name "unconnected-(U5-NC3-Pad25)") (class "Default")
      (node (ref "U5") (pin "25") (pinfunction "NC3_25") (pintype "no_connect"))
    )
  )
)
